# Snickerdoodle_FPGA_JB.net
KiCad netlist of a schematic drawn in Altium Designer
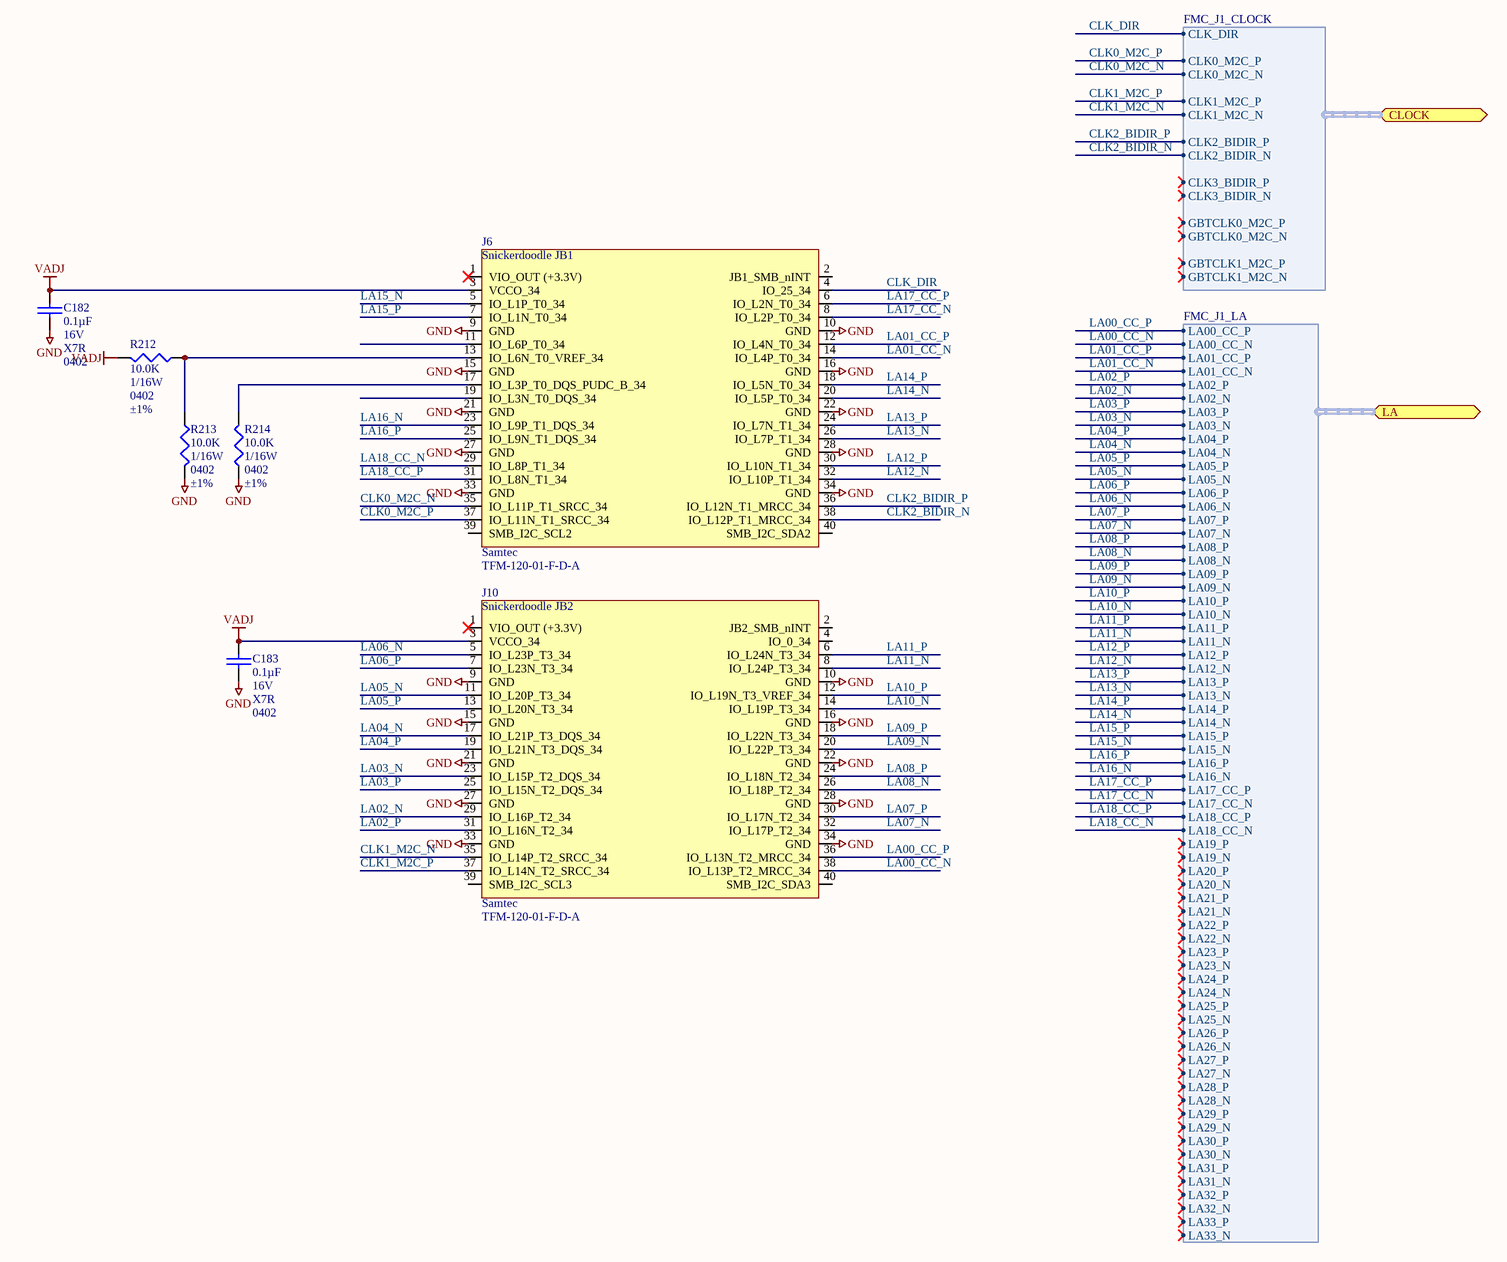
[diagram p0: Snickerdoodle FPGA JB.SchDoc]

(export (version "E")
  (design (tool "Eeschema 10.0.6"))
  (components
    (comp (ref "C182")
      (value "0.1uF")
      (footprint "C_0402")
      (description "CAP CER .10UF 16V X7R 0402")
      (fields
        (field (name "MANUFACTURER") "Murata Electronics North America")
        (field (name "MANUFACTURER PART NUMBER") "GRM155R71C104KA88J")
        (field (name "CAPACITANCE") "0.1µF")
        (field (name "VOLTAGE - RATED") "16V")
        (field (name "TEMPERATURE COEFFICIENT") "X7R")
        (field (name "PACKAGE / CASE") "0402")
      )
      (libsource (lib "Main LibraryX") (part "C_0402_0.1UF_16V"))
    )
    (comp (ref "C183")
      (value "0.1uF")
      (footprint "C_0402")
      (description "CAP CER .10UF 16V X7R 0402")
      (fields
        (field (name "MANUFACTURER") "Murata Electronics North America")
        (field (name "MANUFACTURER PART NUMBER") "GRM155R71C104KA88J")
        (field (name "CAPACITANCE") "0.1µF")
        (field (name "VOLTAGE - RATED") "16V")
        (field (name "TEMPERATURE COEFFICIENT") "X7R")
        (field (name "PACKAGE / CASE") "0402")
      )
      (libsource (lib "Main LibraryX") (part "C_0402_0.1UF_16V"))
    )
    (comp (ref "J6")
      (value "J_SNICKERDOODLE_JB1")
      (footprint "TFM12001-X-D-A")
      (description "SNICKERDOODLE JB1")
      (fields
        (field (name "MANUFCATURER") "Samtec")
        (field (name "MANUFACTURER PART NUMBER") "TFM-120-01-F-D-A")
      )
      (libsource (lib "Cospan Design") (part "J_SNICKERDOODLE_JB1"))
    )
    (comp (ref "J10")
      (value "J_SNICKERDOODLE_JB2")
      (footprint "TFM12001-X-D-A")
      (description "SNICKERDOODLE JB2")
      (fields
        (field (name "MANUFACTURER") "Samtec")
        (field (name "MANUFACTURER PART NUMBER") "TFM-120-01-F-D-A")
      )
      (libsource (lib "Cospan Design") (part "J_SNICKERDOODLE_JB2"))
    )
    (comp (ref "R212")
      (value "R_0402_10.0K")
      (footprint "R_0402")
      (description "RES 10.0K OHM 1/16W 1% 0402 SMD")
      (fields
        (field (name "MANUFACTURER") "Stackpole Electronics Inc")
        (field (name "MANUFACTURER PART NUMBER") "RMCF0402FT10K0")
        (field (name "RESISTANCE IN OHMS") "10.0K")
        (field (name "POWER (WATTS)") "1/16W")
        (field (name "CASE") "0402")
        (field (name "TOLERANCE") "±1%")
      )
      (libsource (lib "Cospan Design") (part "R_0402_10.0K"))
    )
    (comp (ref "R213")
      (value "R_0402_10.0K")
      (footprint "R_0402")
      (description "RES 10.0K OHM 1/16W 1% 0402 SMD")
      (fields
        (field (name "MANUFACTURER") "Stackpole Electronics Inc")
        (field (name "MANUFACTURER PART NUMBER") "RMCF0402FT10K0")
        (field (name "RESISTANCE IN OHMS") "10.0K")
        (field (name "POWER (WATTS)") "1/16W")
        (field (name "CASE") "0402")
        (field (name "TOLERANCE") "±1%")
      )
      (libsource (lib "Cospan Design") (part "R_0402_10.0K"))
    )
    (comp (ref "R214")
      (value "R_0402_10.0K")
      (footprint "R_0402")
      (description "RES 10.0K OHM 1/16W 1% 0402 SMD")
      (fields
        (field (name "MANUFACTURER") "Stackpole Electronics Inc")
        (field (name "MANUFACTURER PART NUMBER") "RMCF0402FT10K0")
        (field (name "RESISTANCE IN OHMS") "10.0K")
        (field (name "POWER (WATTS)") "1/16W")
        (field (name "CASE") "0402")
        (field (name "TOLERANCE") "±1%")
      )
      (libsource (lib "Cospan Design") (part "R_0402_10.0K"))
    )
  )
  (nets
    (net (code "3") (name "/CLK0_M2C_N") (class "Default")
      (node (ref "J6") (pin "35") (pinfunction "IO_L11P_T1_SRCC_34_35") (pintype "passive"))
    )
    (net (code "4") (name "/CLK0_M2C_P") (class "Default")
      (node (ref "J6") (pin "37") (pinfunction "IO_L11N_T1_SRCC_34_37") (pintype "passive"))
    )
    (net (code "5") (name "/CLK1_M2C_N") (class "Default")
      (node (ref "J10") (pin "35") (pinfunction "IO_L14P_T2_SRCC_34_35") (pintype "passive"))
    )
    (net (code "6") (name "/CLK1_M2C_P") (class "Default")
      (node (ref "J10") (pin "37") (pinfunction "IO_L14N_T2_SRCC_34_37") (pintype "passive"))
    )
    (net (code "7") (name "/CLK2_BIDIR_N") (class "Default")
      (node (ref "J6") (pin "38") (pinfunction "IO_L12P_T1_MRCC_34_38") (pintype "passive"))
    )
    (net (code "8") (name "/CLK2_BIDIR_P") (class "Default")
      (node (ref "J6") (pin "36") (pinfunction "IO_L12N_T1_MRCC_34_36") (pintype "passive"))
    )
    (net (code "9") (name "/CLK_DIR") (class "Default")
      (node (ref "J6") (pin "4") (pinfunction "IO_25_34_4") (pintype "passive"))
    )
    (net (code "10") (name "/LA00_CC_N") (class "Default")
      (node (ref "J10") (pin "38") (pinfunction "IO_L13P_T2_MRCC_34_38") (pintype "passive"))
    )
    (net (code "11") (name "/LA00_CC_P") (class "Default")
      (node (ref "J10") (pin "36") (pinfunction "IO_L13N_T2_MRCC_34_36") (pintype "passive"))
    )
    (net (code "12") (name "/LA01_CC_N") (class "Default")
      (node (ref "J6") (pin "14") (pinfunction "IO_L4P_T0_34_14") (pintype "passive"))
    )
    (net (code "13") (name "/LA01_CC_P") (class "Default")
      (node (ref "J6") (pin "12") (pinfunction "IO_L4N_T0_34_12") (pintype "passive"))
    )
    (net (code "14") (name "/LA02_N") (class "Default")
      (node (ref "J10") (pin "29") (pinfunction "IO_L16P_T2_34_29") (pintype "passive"))
    )
    (net (code "15") (name "/LA02_P") (class "Default")
      (node (ref "J10") (pin "31") (pinfunction "IO_L16N_T2_34_31") (pintype "passive"))
    )
    (net (code "16") (name "/LA03_N") (class "Default")
      (node (ref "J10") (pin "23") (pinfunction "IO_L15P_T2_DQS_34_23") (pintype "passive"))
    )
    (net (code "17") (name "/LA03_P") (class "Default")
      (node (ref "J10") (pin "25") (pinfunction "IO_L15N_T2_DQS_34_25") (pintype "passive"))
    )
    (net (code "18") (name "/LA04_N") (class "Default")
      (node (ref "J10") (pin "17") (pinfunction "IO_L21P_T3_DQS_34_17") (pintype "passive"))
    )
    (net (code "19") (name "/LA04_P") (class "Default")
      (node (ref "J10") (pin "19") (pinfunction "IO_L21N_T3_DQS_34_19") (pintype "passive"))
    )
    (net (code "20") (name "/LA05_N") (class "Default")
      (node (ref "J10") (pin "11") (pinfunction "IO_L20P_T3_34_11") (pintype "passive"))
    )
    (net (code "21") (name "/LA05_P") (class "Default")
      (node (ref "J10") (pin "13") (pinfunction "IO_L20N_T3_34_13") (pintype "passive"))
    )
    (net (code "22") (name "/LA06_N") (class "Default")
      (node (ref "J10") (pin "5") (pinfunction "IO_L23P_T3_34_5") (pintype "passive"))
    )
    (net (code "23") (name "/LA06_P") (class "Default")
      (node (ref "J10") (pin "7") (pinfunction "IO_L23N_T3_34_7") (pintype "passive"))
    )
    (net (code "24") (name "/LA07_N") (class "Default")
      (node (ref "J10") (pin "32") (pinfunction "IO_L17P_T2_34_32") (pintype "passive"))
    )
    (net (code "25") (name "/LA07_P") (class "Default")
      (node (ref "J10") (pin "30") (pinfunction "IO_L17N_T2_34_30") (pintype "passive"))
    )
    (net (code "26") (name "/LA08_N") (class "Default")
      (node (ref "J10") (pin "26") (pinfunction "IO_L18P_T2_34_26") (pintype "passive"))
    )
    (net (code "27") (name "/LA08_P") (class "Default")
      (node (ref "J10") (pin "24") (pinfunction "IO_L18N_T2_34_24") (pintype "passive"))
    )
    (net (code "28") (name "/LA09_N") (class "Default")
      (node (ref "J10") (pin "20") (pinfunction "IO_L22P_T3_34_20") (pintype "passive"))
    )
    (net (code "29") (name "/LA09_P") (class "Default")
      (node (ref "J10") (pin "18") (pinfunction "IO_L22N_T3_34_18") (pintype "passive"))
    )
    (net (code "30") (name "/LA10_N") (class "Default")
      (node (ref "J10") (pin "14") (pinfunction "IO_L19P_T3_34_14") (pintype "passive"))
    )
    (net (code "31") (name "/LA10_P") (class "Default")
      (node (ref "J10") (pin "12") (pinfunction "IO_L19N_T3_VREF_34_12") (pintype "passive"))
    )
    (net (code "32") (name "/LA11_N") (class "Default")
      (node (ref "J10") (pin "8") (pinfunction "IO_L24P_T3_34_8") (pintype "passive"))
    )
    (net (code "33") (name "/LA11_P") (class "Default")
      (node (ref "J10") (pin "6") (pinfunction "IO_L24N_T3_34_6") (pintype "passive"))
    )
    (net (code "34") (name "/LA12_N") (class "Default")
      (node (ref "J6") (pin "32") (pinfunction "IO_L10P_T1_34_32") (pintype "passive"))
    )
    (net (code "35") (name "/LA12_P") (class "Default")
      (node (ref "J6") (pin "30") (pinfunction "IO_L10N_T1_34_30") (pintype "passive"))
    )
    (net (code "36") (name "/LA13_N") (class "Default")
      (node (ref "J6") (pin "26") (pinfunction "IO_L7P_T1_34_26") (pintype "passive"))
    )
    (net (code "37") (name "/LA13_P") (class "Default")
      (node (ref "J6") (pin "24") (pinfunction "IO_L7N_T1_34_24") (pintype "passive"))
    )
    (net (code "38") (name "/LA14_N") (class "Default")
      (node (ref "J6") (pin "20") (pinfunction "IO_L5P_T0_34_20") (pintype "passive"))
    )
    (net (code "39") (name "/LA14_P") (class "Default")
      (node (ref "J6") (pin "18") (pinfunction "IO_L5N_T0_34_18") (pintype "passive"))
    )
    (net (code "40") (name "/LA15_N") (class "Default")
      (node (ref "J6") (pin "5") (pinfunction "IO_L1P_T0_34_5") (pintype "passive"))
    )
    (net (code "41") (name "/LA15_P") (class "Default")
      (node (ref "J6") (pin "7") (pinfunction "IO_L1N_T0_34_7") (pintype "passive"))
    )
    (net (code "42") (name "/LA16_N") (class "Default")
      (node (ref "J6") (pin "23") (pinfunction "IO_L9P_T1_DQS_34_23") (pintype "passive"))
    )
    (net (code "43") (name "/LA16_P") (class "Default")
      (node (ref "J6") (pin "25") (pinfunction "IO_L9N_T1_DQS_34_25") (pintype "passive"))
    )
    (net (code "44") (name "/LA17_CC_N") (class "Default")
      (node (ref "J6") (pin "8") (pinfunction "IO_L2P_T0_34_8") (pintype "passive"))
    )
    (net (code "45") (name "/LA17_CC_P") (class "Default")
      (node (ref "J6") (pin "6") (pinfunction "IO_L2N_T0_34_6") (pintype "passive"))
    )
    (net (code "46") (name "/LA18_CC_N") (class "Default")
      (node (ref "J6") (pin "29") (pinfunction "IO_L8P_T1_34_29") (pintype "passive"))
    )
    (net (code "47") (name "/LA18_CC_P") (class "Default")
      (node (ref "J6") (pin "31") (pinfunction "IO_L8N_T1_34_31") (pintype "passive"))
    )
    (net (code "50") (name "GND") (class "Default")
      (node (ref "C182") (pin "1") (pinfunction "1_1") (pintype "passive"))
      (node (ref "C183") (pin "1") (pinfunction "1_1") (pintype "passive"))
      (node (ref "J10") (pin "10") (pinfunction "GND_10") (pintype "passive"))
      (node (ref "J10") (pin "15") (pinfunction "GND_15") (pintype "passive"))
      (node (ref "J10") (pin "16") (pinfunction "GND_16") (pintype "passive"))
      (node (ref "J10") (pin "21") (pinfunction "GND_21") (pintype "passive"))
      (node (ref "J10") (pin "22") (pinfunction "GND_22") (pintype "passive"))
      (node (ref "J10") (pin "27") (pinfunction "GND_27") (pintype "passive"))
      (node (ref "J10") (pin "28") (pinfunction "GND_28") (pintype "passive"))
      (node (ref "J10") (pin "33") (pinfunction "GND_33") (pintype "passive"))
      (node (ref "J10") (pin "34") (pinfunction "GND_34") (pintype "passive"))
      (node (ref "J10") (pin "9") (pinfunction "GND_9") (pintype "passive"))
      (node (ref "J6") (pin "10") (pinfunction "GND_10") (pintype "passive"))
      (node (ref "J6") (pin "15") (pinfunction "GND_15") (pintype "passive"))
      (node (ref "J6") (pin "16") (pinfunction "GND_16") (pintype "passive"))
      (node (ref "J6") (pin "21") (pinfunction "GND_21") (pintype "passive"))
      (node (ref "J6") (pin "22") (pinfunction "GND_22") (pintype "passive"))
      (node (ref "J6") (pin "27") (pinfunction "GND_27") (pintype "passive"))
      (node (ref "J6") (pin "28") (pinfunction "GND_28") (pintype "passive"))
      (node (ref "J6") (pin "33") (pinfunction "GND_33") (pintype "passive"))
      (node (ref "J6") (pin "34") (pinfunction "GND_34") (pintype "passive"))
      (node (ref "J6") (pin "9") (pinfunction "GND_9") (pintype "passive"))
      (node (ref "R213") (pin "1") (pinfunction "1_1") (pintype "passive"))
      (node (ref "R214") (pin "2") (pinfunction "2_2") (pintype "passive"))
    )
    (net (code "51") (name "Net-(J6-IO_L3P_T0_DQS_PUDC_B_34)") (class "Default")
      (node (ref "J6") (pin "17") (pinfunction "IO_L3P_T0_DQS_PUDC_B_34_17") (pintype "passive"))
      (node (ref "R214") (pin "1") (pinfunction "1_1") (pintype "passive"))
    )
    (net (code "52") (name "Net-(J6-IO_L6N_T0_VREF_34)") (class "Default")
      (node (ref "J6") (pin "13") (pinfunction "IO_L6N_T0_VREF_34_13") (pintype "passive"))
      (node (ref "R212") (pin "2") (pinfunction "2_2") (pintype "passive"))
      (node (ref "R213") (pin "2") (pinfunction "2_2") (pintype "passive"))
    )
    (net (code "53") (name "VADJ") (class "Default")
      (node (ref "C182") (pin "2") (pinfunction "2_2") (pintype "passive"))
      (node (ref "C183") (pin "2") (pinfunction "2_2") (pintype "passive"))
      (node (ref "J10") (pin "3") (pinfunction "VCCO_34_3") (pintype "passive"))
      (node (ref "J6") (pin "3") (pinfunction "VCCO_34_3") (pintype "passive"))
      (node (ref "R212") (pin "1") (pinfunction "1_1") (pintype "passive"))
    )
    (net (code "54") (name "unconnected-(J6-IO_L3N_T0_DQS_34-Pad19)") (class "Default")
      (node (ref "J6") (pin "19") (pinfunction "IO_L3N_T0_DQS_34_19") (pintype "passive"))
    )
    (net (code "55") (name "unconnected-(J6-IO_L6P_T0_34-Pad11)") (class "Default")
      (node (ref "J6") (pin "11") (pinfunction "IO_L6P_T0_34_11") (pintype "passive"))
    )
    (net (code "56") (name "unconnected-(J6-JB1_SMB_nINT-Pad2)") (class "Default")
      (node (ref "J6") (pin "2") (pinfunction "JB1_SMB_nINT_2") (pintype "passive"))
    )
    (net (code "57") (name "unconnected-(J6-SMB_I2C_SCL2-Pad39)") (class "Default")
      (node (ref "J6") (pin "39") (pinfunction "SMB_I2C_SCL2_39") (pintype "passive"))
    )
    (net (code "58") (name "unconnected-(J6-SMB_I2C_SDA2-Pad40)") (class "Default")
      (node (ref "J6") (pin "40") (pinfunction "SMB_I2C_SDA2_40") (pintype "passive"))
    )
    (net (code "59") (name "unconnected-(J6-VIO_OUT_(+3.3V)-Pad1)") (class "Default")
      (node (ref "J6") (pin "1") (pinfunction "VIO_OUT_(+3.3V)_1") (pintype "passive+no_connect"))
    )
    (net (code "60") (name "unconnected-(J10-IO_0_34-Pad4)") (class "Default")
      (node (ref "J10") (pin "4") (pinfunction "IO_0_34_4") (pintype "passive"))
    )
    (net (code "61") (name "unconnected-(J10-JB2_SMB_nINT-Pad2)") (class "Default")
      (node (ref "J10") (pin "2") (pinfunction "JB2_SMB_nINT_2") (pintype "passive"))
    )
    (net (code "62") (name "unconnected-(J10-SMB_I2C_SCL3-Pad39)") (class "Default")
      (node (ref "J10") (pin "39") (pinfunction "SMB_I2C_SCL3_39") (pintype "passive"))
    )
    (net (code "63") (name "unconnected-(J10-SMB_I2C_SDA3-Pad40)") (class "Default")
      (node (ref "J10") (pin "40") (pinfunction "SMB_I2C_SDA3_40") (pintype "passive"))
    )
    (net (code "64") (name "unconnected-(J10-VIO_OUT_(+3.3V)-Pad1)") (class "Default")
      (node (ref "J10") (pin "1") (pinfunction "VIO_OUT_(+3.3V)_1") (pintype "passive+no_connect"))
    )
  )
)
